# bat-phone_Dodo_v0_3.net
KiCad netlist of a schematic drawn in EAGLE
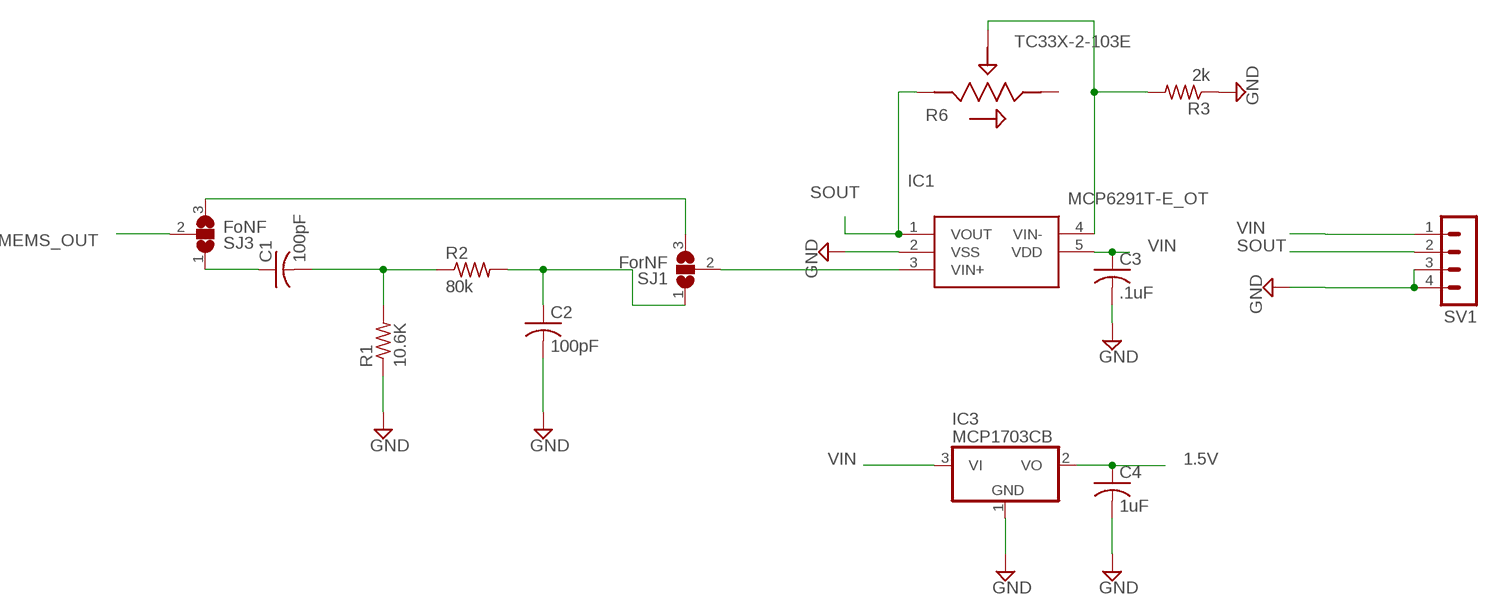
[diagram p0: schematic, sheet 1]

(export (version "E")
  (design (tool "Eeschema 10.0.6"))
  (components
    (comp (ref "C1")
      (value "100pF")
      (footprint "eagle-import:C0603")
      (libsource (lib "eagle-import") (part "C-USC0603"))
    )
    (comp (ref "C2")
      (value "100pF")
      (footprint "eagle-import:C0603")
      (libsource (lib "eagle-import") (part "C-USC0603"))
    )
    (comp (ref "C3")
      (value ".1uF")
      (footprint "eagle-import:C0603")
      (fields (field (name "SPICEPREFIX") "C"))
      (libsource (lib "eagle-import") (part "C-USC0603"))
    )
    (comp (ref "C4")
      (value "1uF")
      (footprint "eagle-import:C0603")
      (libsource (lib "eagle-import") (part "C-USC0603"))
    )
    (comp (ref "IC1")
      (value "MCP6291T-E_OT")
      (footprint "eagle-import:SOT95P280X145-5N")
      (fields
        (field (name "MANUFACTURER_PART_NUMBER") "MCP6291T-E/OT")
        (field (name "MOUSER_PART_NUMBER") "579-MCP6291T-E/OT")
        (field (name "RS_PART_NUMBER") "8896089")
      )
      (libsource (lib "eagle-import") (part "MCP6291T-E_OT"))
    )
    (comp (ref "IC3")
      (value "MCP1703CB")
      (footprint "eagle-import:SOT23")
      (libsource (lib "eagle-import") (part "MCP1703CB"))
    )
    (comp (ref "R1")
      (value "10.6K")
      (footprint "eagle-import:R0603")
      (libsource (lib "eagle-import") (part "R-US_R0603"))
    )
    (comp (ref "R2")
      (value "80k")
      (footprint "eagle-import:R0603")
      (libsource (lib "eagle-import") (part "R-US_R0603"))
    )
    (comp (ref "R3")
      (value "2k")
      (footprint "eagle-import:R0603")
      (libsource (lib "eagle-import") (part "R-US_R0603"))
    )
    (comp (ref "R6")
      (value "TC33X-2-103E")
      (footprint "eagle-import:35WR")
      (fields (field (name "MF") "Bourns"))
      (libsource (lib "eagle-import") (part "TC33X-2-103E"))
    )
    (comp (ref "SJ1")
      (value "ForNF")
      (footprint "eagle-import:SJ_2")
      (libsource (lib "eagle-import") (part "SJ2W"))
    )
    (comp (ref "SJ3")
      (value "FoNF")
      (footprint "eagle-import:SJ_2")
      (libsource (lib "eagle-import") (part "SJ2W"))
    )
    (comp (ref "SV1")
      (value "MA04-1")
      (footprint "eagle-import:MA04-1")
      (libsource (lib "eagle-import") (part "MA04-1"))
    )
  )
  (nets
    (net (code "1") (name "/1.5V") (class "Default")
      (node (ref "C4") (pin "1") (pinfunction "1_1") (pintype "passive"))
      (node (ref "IC3") (pin "2") (pinfunction "VO_2") (pintype "passive"))
    )
    (net (code "2") (name "/MEMS_OUT") (class "Default")
      (node (ref "SJ3") (pin "2") (pinfunction "2_2") (pintype "passive"))
    )
    (net (code "3") (name "/SOUT") (class "Default")
      (node (ref "IC1") (pin "1") (pinfunction "VOUT_1") (pintype "bidirectional"))
      (node (ref "R6") (pin "1") (pinfunction "1_1") (pintype "passive"))
      (node (ref "SV1") (pin "2") (pinfunction "2_2") (pintype "passive"))
    )
    (net (code "4") (name "/VIN") (class "Default")
      (node (ref "C3") (pin "1") (pinfunction "1_1") (pintype "passive"))
      (node (ref "IC1") (pin "5") (pinfunction "VDD_5") (pintype "bidirectional"))
      (node (ref "IC3") (pin "3") (pinfunction "VI_3") (pintype "input"))
      (node (ref "SV1") (pin "1") (pinfunction "1_1") (pintype "passive"))
    )
    (net (code "5") (name "GND") (class "Default")
      (node (ref "C2") (pin "2") (pinfunction "2_2") (pintype "passive"))
      (node (ref "C3") (pin "2") (pinfunction "2_2") (pintype "passive"))
      (node (ref "C4") (pin "2") (pinfunction "2_2") (pintype "passive"))
      (node (ref "IC1") (pin "2") (pinfunction "VSS_2") (pintype "bidirectional"))
      (node (ref "IC3") (pin "1") (pinfunction "GND_1") (pintype "passive"))
      (node (ref "R1") (pin "1") (pinfunction "1_1") (pintype "passive"))
      (node (ref "R3") (pin "1") (pinfunction "1_1") (pintype "passive"))
      (node (ref "SV1") (pin "3") (pinfunction "3_3") (pintype "passive"))
      (node (ref "SV1") (pin "4") (pinfunction "4_4") (pintype "passive"))
    )
    (net (code "6") (name "Net-(C1-Pad1)") (class "Default")
      (node (ref "C1") (pin "1") (pinfunction "1_1") (pintype "passive"))
      (node (ref "SJ3") (pin "1") (pinfunction "1_1") (pintype "passive"))
    )
    (net (code "7") (name "Net-(C1-Pad2)") (class "Default")
      (node (ref "C1") (pin "2") (pinfunction "2_2") (pintype "passive"))
      (node (ref "R1") (pin "2") (pinfunction "2_2") (pintype "passive"))
      (node (ref "R2") (pin "1") (pinfunction "1_1") (pintype "passive"))
    )
    (net (code "8") (name "Net-(C2-Pad1)") (class "Default")
      (node (ref "C2") (pin "1") (pinfunction "1_1") (pintype "passive"))
      (node (ref "R2") (pin "2") (pinfunction "2_2") (pintype "passive"))
      (node (ref "SJ1") (pin "1") (pinfunction "1_1") (pintype "passive"))
    )
    (net (code "9") (name "Net-(IC1-VIN+)") (class "Default")
      (node (ref "IC1") (pin "3") (pinfunction "VIN+_3") (pintype "bidirectional"))
      (node (ref "SJ1") (pin "2") (pinfunction "2_2") (pintype "passive"))
    )
    (net (code "10") (name "Net-(IC1-VIN-)") (class "Default")
      (node (ref "IC1") (pin "4") (pinfunction "VIN-_4") (pintype "bidirectional"))
      (node (ref "R3") (pin "2") (pinfunction "2_2") (pintype "passive"))
      (node (ref "R6") (pin "2") (pinfunction "2_2") (pintype "passive"))
    )
    (net (code "11") (name "Net-(SJ1-Pad3)") (class "Default")
      (node (ref "SJ1") (pin "3") (pinfunction "3_3") (pintype "passive"))
      (node (ref "SJ3") (pin "3") (pinfunction "3_3") (pintype "passive"))
    )
    (net (code "12") (name "unconnected-(R6-Pad3)") (class "Default")
      (node (ref "R6") (pin "3") (pinfunction "3_3") (pintype "passive"))
    )
  )
)
